# 08.net
KiCad netlist of a schematic drawn in Altium Designer
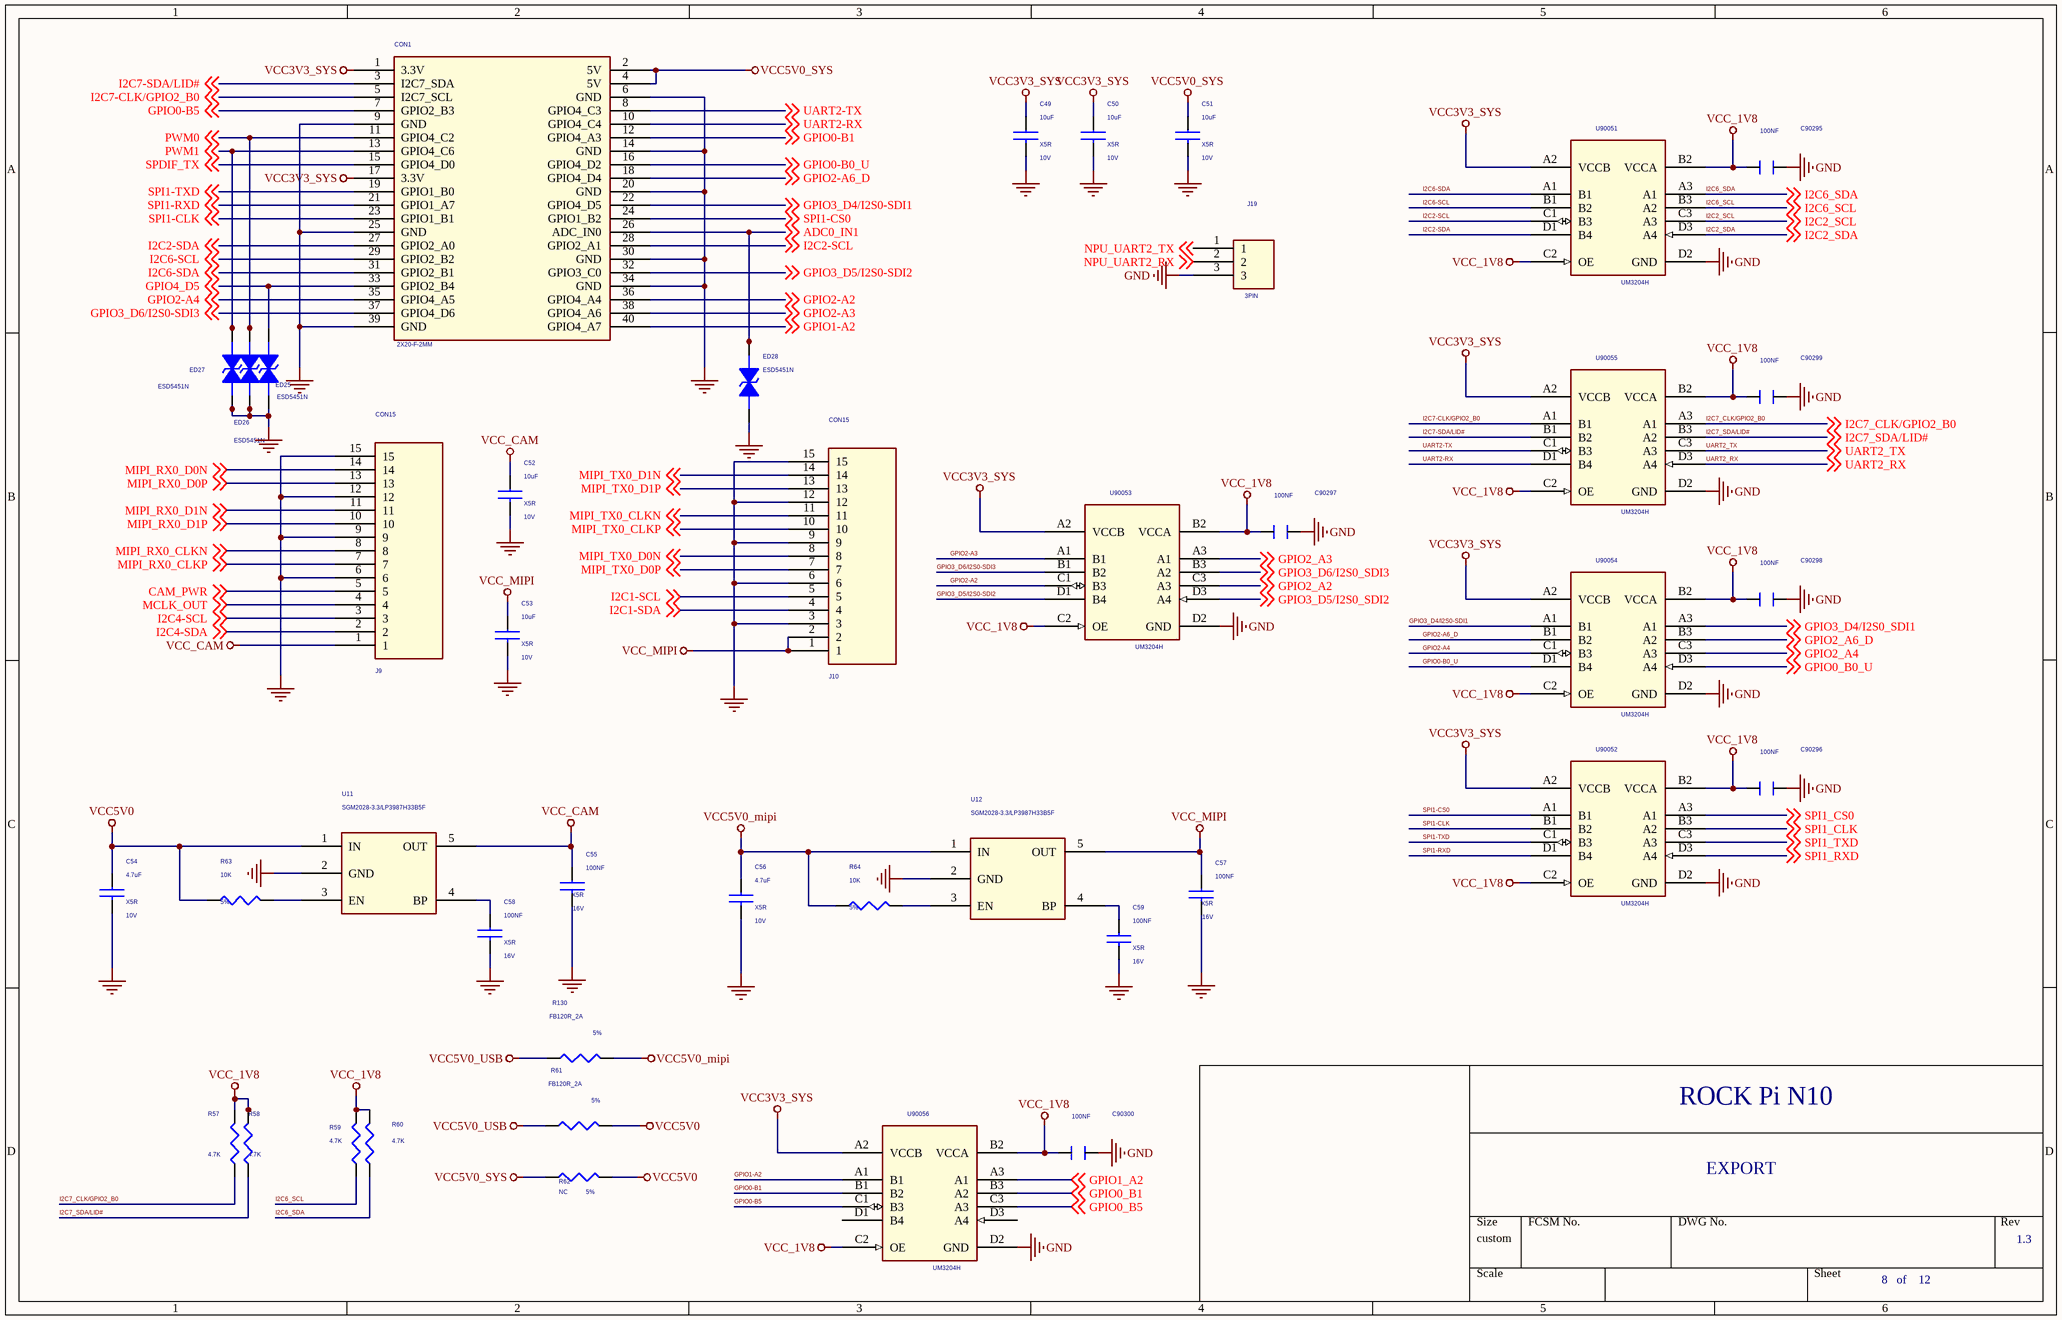
[diagram p0: 08.SchDoc]

(export (version "E")
  (design (tool "Eeschema 10.0.6"))
  (components
    (comp (ref "C49")
      (value "10uF")
      (footprint "C0603")
      (description "cap,10.00uF,+/-10%,10V,X5R,C0805")
      (fields
        (field (name "DIELECTRIC") "X5R")
        (field (name "VOLTAGE") "10V")
        (field (name "MANUFACTURER") "TDK")
        (field (name "TOLERANCE") "10%")
        (field (name "CREATED BY") "JJJ")
      )
      (libsource (lib "*") (part "CAP NP_2"))
    )
    (comp (ref "C50")
      (value "10uF")
      (footprint "C0603")
      (description "cap,10.00uF,+/-10%,10V,X5R,C0805")
      (fields
        (field (name "DIELECTRIC") "X5R")
        (field (name "VOLTAGE") "10V")
        (field (name "TOLERANCE") "10%")
        (field (name "MANUFACTURER") "TDK")
        (field (name "CREATED BY") "JJJ")
      )
      (libsource (lib "*") (part "CAP NP_2"))
    )
    (comp (ref "C51")
      (value "10uF")
      (footprint "C0603")
      (description "cap,10.00uF,+/-10%,10V,X5R,C0805")
      (fields
        (field (name "DIELECTRIC") "X5R")
        (field (name "VOLTAGE") "10V")
        (field (name "TOLERANCE") "10%")
        (field (name "MANUFACTURER") "TDK")
        (field (name "CREATED BY") "JJJ")
      )
      (libsource (lib "*") (part "CAP NP_2"))
    )
    (comp (ref "C52")
      (value "10uF")
      (footprint "C0603")
      (description "cap,10.00uF,+/-10%,10V,X5R,C0805")
      (fields
        (field (name "DIELECTRIC") "X5R")
        (field (name "VOLTAGE") "10V")
        (field (name "MANUFACTURER") "TDK")
        (field (name "TOLERANCE") "10%")
        (field (name "CREATED BY") "JJJ")
      )
      (libsource (lib "*") (part "CAP NP_2"))
    )
    (comp (ref "C53")
      (value "10uF")
      (footprint "C0603")
      (description "cap,10.00uF,+/-10%,10V,X5R,C0805")
      (fields
        (field (name "DIELECTRIC") "X5R")
        (field (name "VOLTAGE") "10V")
        (field (name "TOLERANCE") "10%")
        (field (name "MANUFACTURER") "TDK")
        (field (name "CREATED BY") "JJJ")
      )
      (libsource (lib "*") (part "CAP NP_2"))
    )
    (comp (ref "C54")
      (value "4.7uF")
      (footprint "C0603")
      (description "cap,4.70uF,+/-10%,10V,X5R,C0603")
      (fields
        (field (name "DIELECTRIC") "X5R")
        (field (name "VOLTAGE") "10V")
        (field (name "TOLERANCE") "10%")
        (field (name "MANUFACTURER") "TDK")
        (field (name "CREATED BY") "JJJ")
      )
      (libsource (lib "*") (part "CAP NP_2"))
    )
    (comp (ref "C55")
      (value "100NF")
      (footprint "C0402")
      (description "cap,100.00nF,+/-10%,16V,X5R,C0402")
      (fields
        (field (name "DIELECTRIC") "X5R")
        (field (name "VOLTAGE") "16V")
        (field (name "TOLERANCE") "10%")
        (field (name "MANUFACTURER") "TDK")
        (field (name "CREATED BY") "JJJ")
      )
      (libsource (lib "*") (part "CAP NP_2"))
    )
    (comp (ref "C56")
      (value "4.7uF")
      (footprint "C0603")
      (description "cap,4.70uF,+/-10%,10V,X5R,C0603")
      (fields
        (field (name "DIELECTRIC") "X5R")
        (field (name "VOLTAGE") "10V")
        (field (name "TOLERANCE") "10%")
        (field (name "MANUFACTURER") "TDK")
        (field (name "CREATED BY") "JJJ")
      )
      (libsource (lib "*") (part "CAP NP_2"))
    )
    (comp (ref "C57")
      (value "100NF")
      (footprint "C0402")
      (description "cap,100.00nF,+/-10%,16V,X5R,C0402")
      (fields
        (field (name "DIELECTRIC") "X5R")
        (field (name "VOLTAGE") "16V")
        (field (name "MANUFACTURER") "TDK")
        (field (name "TOLERANCE") "10%")
        (field (name "CREATED BY") "JJJ")
      )
      (libsource (lib "*") (part "CAP NP_2"))
    )
    (comp (ref "C58")
      (value "100NF")
      (footprint "C0402")
      (description "cap,100.00nF,+/-10%,16V,X5R,C0402")
      (fields
        (field (name "DIELECTRIC") "X5R")
        (field (name "VOLTAGE") "16V")
        (field (name "TOLERANCE") "10%")
        (field (name "MANUFACTURER") "TDK")
        (field (name "CREATED BY") "JJJ")
      )
      (libsource (lib "*") (part "CAP NP_2"))
    )
    (comp (ref "C59")
      (value "100NF")
      (footprint "C0402")
      (description "cap,100.00nF,+/-10%,16V,X5R,C0402")
      (fields
        (field (name "DIELECTRIC") "X5R")
        (field (name "VOLTAGE") "16V")
        (field (name "TOLERANCE") "10%")
        (field (name "MANUFACTURER") "TDK")
        (field (name "CREATED BY") "JJJ")
      )
      (libsource (lib "*") (part "CAP NP_2"))
    )
    (comp (ref "C90295") (value "100NF") (footprint "C0402") (libsource (lib "*") (part "CAPACITOR_0")))
    (comp (ref "C90296") (value "100NF") (footprint "C0402") (libsource (lib "*") (part "CAPACITOR_0")))
    (comp (ref "C90297") (value "100NF") (footprint "C0402") (libsource (lib "*") (part "CAPACITOR_0")))
    (comp (ref "C90298") (value "100NF") (footprint "C0402") (libsource (lib "*") (part "CAPACITOR_0")))
    (comp (ref "C90299") (value "100NF") (footprint "C0402") (libsource (lib "*") (part "CAPACITOR_0")))
    (comp (ref "C90300") (value "100NF") (footprint "C0402") (libsource (lib "*") (part "CAPACITOR_0")))
    (comp (ref "CON1")
      (value "2X20-F-2MM")
      (footprint "DIP40PIN-2.54MM_FX")
      (libsource (lib "*") (part "CN_4"))
    )
    (comp (ref "ED25")
      (value "ESD5451N")
      (footprint "ESD0402")
      (description "1-Line, Bi-directional, Transient Voltage Suppressors.17.5pF.")
      (fields (field (name "MANUFACTURER") "WillSemi(韦尔半导体)") (field (name "CREATED BY") "JJJ"))
      (libsource (lib "*") (part "DIODE BI_DIR TRIG_0"))
    )
    (comp (ref "ED26")
      (value "ESD5451N")
      (footprint "ESD0402")
      (description "1-Line, Bi-directional, Transient Voltage Suppressors.17.5pF.")
      (fields (field (name "MANUFACTURER") "WillSemi(韦尔半导体)") (field (name "CREATED BY") "JJJ"))
      (libsource (lib "*") (part "DIODE BI_DIR TRIG_0"))
    )
    (comp (ref "ED27")
      (value "ESD5451N")
      (footprint "ESD0402")
      (description "1-Line, Bi-directional, Transient Voltage Suppressors.17.5pF.")
      (fields (field (name "MANUFACTURER") "WillSemi(韦尔半导体)") (field (name "CREATED BY") "JJJ"))
      (libsource (lib "*") (part "DIODE BI_DIR TRIG_0"))
    )
    (comp (ref "ED28")
      (value "ESD5451N")
      (footprint "ESD0402")
      (description "1-Line, Bi-directional, Transient Voltage Suppressors.17.5pF.")
      (fields (field (name "MANUFACTURER") "WillSemi(韦尔半导体)") (field (name "CREATED BY") "JJJ"))
      (libsource (lib "*") (part "DIODE BI_DIR TRIG_0"))
    )
    (comp (ref "J9") (value "CON15") (footprint "FPC15PIN-1.0MM-LS") (libsource (lib "*") (part "CON15_0")))
    (comp (ref "J10") (value "CON15") (footprint "FPC15PIN-1.0MM-LS") (libsource (lib "*") (part "CON15_0")))
    (comp (ref "J19") (value "3PIN") (footprint "3PIN") (libsource (lib "*") (part "3PIN")))
    (comp (ref "R57") (value "4.7K") (footprint "R0402") (libsource (lib "*") (part "R_2")))
    (comp (ref "R58") (value "4.7K") (footprint "R0402") (libsource (lib "*") (part "R_2")))
    (comp (ref "R59") (value "4.7K") (footprint "R0402") (libsource (lib "*") (part "R_2")))
    (comp (ref "R60") (value "4.7K") (footprint "R0402") (libsource (lib "*") (part "R_2")))
    (comp (ref "R61")
      (value "FB120R_2A")
      (footprint "R0402")
      (description "通用厚膜电阻,10K,+/-5%,R0402,1/16W.")
      (fields
        (field (name "TOLERANCE") "5%")
        (field (name "MANUFACTURER") "YAGEO")
        (field (name "CREATED BY") "YTL")
      )
      (libsource (lib "*") (part "RESISTOR_3"))
    )
    (comp (ref "R62")
      (value "NC")
      (footprint "R0402")
      (description "通用厚膜电阻,10K,+/-5%,R0402,1/16W.")
      (fields
        (field (name "TOLERANCE") "5%")
        (field (name "MANUFACTURER") "YAGEO")
        (field (name "CREATED BY") "YTL")
      )
      (libsource (lib "*") (part "RESISTOR_3"))
    )
    (comp (ref "R63")
      (value "10K")
      (footprint "R0402")
      (description "通用厚膜电阻,10K,+/-5%,R0402,1/16W.")
      (fields
        (field (name "TOLERANCE") "5%")
        (field (name "MANUFACTURER") "YAGEO")
        (field (name "CREATED BY") "YTL")
      )
      (libsource (lib "*") (part "RESISTOR_3"))
    )
    (comp (ref "R64")
      (value "10K")
      (footprint "R0402")
      (description "通用厚膜电阻,10K,+/-5%,R0402,1/16W.")
      (fields
        (field (name "TOLERANCE") "5%")
        (field (name "MANUFACTURER") "YAGEO")
        (field (name "CREATED BY") "YTL")
      )
      (libsource (lib "*") (part "RESISTOR_3"))
    )
    (comp (ref "R130")
      (value "FB120R_2A")
      (footprint "R0402")
      (description "通用厚膜电阻,10K,+/-5%,R0402,1/16W.")
      (fields
        (field (name "TOLERANCE") "5%")
        (field (name "MANUFACTURER") "YAGEO")
        (field (name "CREATED BY") "YTL")
      )
      (libsource (lib "*") (part "RESISTOR_3"))
    )
    (comp (ref "U11")
      (value "SGM2028-3.3/LP3987H33B5F")
      (footprint "SOT_23_5")
      (description "500mA, Low Dropout, Low Noise Ultra-Fast Without Bypass Capacitor CMOS LDO Regulator")
      (fields (field (name "MANUFACTURER") "Richtek（立錡）") (field (name "CREATED BY") "JJJ"))
      (libsource (lib "*") (part "LDO_PT5108"))
    )
    (comp (ref "U12")
      (value "SGM2028-3.3/LP3987H33B5F")
      (footprint "SOT_23_5")
      (description "500mA, Low Dropout, Low Noise Ultra-Fast Without Bypass Capacitor CMOS LDO Regulator")
      (fields (field (name "MANUFACTURER") "Richtek（立錡）") (field (name "CREATED BY") "JJJ"))
      (libsource (lib "*") (part "LDO_PT5108"))
    )
    (comp (ref "U90051")
      (value "UM3204H")
      (footprint "CSP-12")
      (description "4-bit Bi-directional Level Shifter UM3204H")
      (fields (field (name "PART NUMBER") "PI4ULS5V104GAEX"))
      (libsource (lib "*") (part "MP2610_0"))
    )
    (comp (ref "U90052")
      (value "UM3204H")
      (footprint "CSP-12")
      (description "4-bit Bi-directional Level Shifter  UM3204H")
      (fields (field (name "PART NUMBER") "PI4ULS5V104GAEX"))
      (libsource (lib "*") (part "MP2610_0"))
    )
    (comp (ref "U90053")
      (value "UM3204H")
      (footprint "CSP-12")
      (description "4-bit Bi-directional Level Shifter  UM3204H")
      (fields (field (name "PART NUMBER") "PI4ULS5V104GAEX"))
      (libsource (lib "*") (part "MP2610_0"))
    )
    (comp (ref "U90054")
      (value "UM3204H")
      (footprint "CSP-12")
      (description "4-bit Bi-directional Level Shifter   UM3204H")
      (fields (field (name "PART NUMBER") "PI4ULS5V104GAEX"))
      (libsource (lib "*") (part "MP2610_0"))
    )
    (comp (ref "U90055")
      (value "UM3204H")
      (footprint "CSP-12")
      (description "4-bit Bi-directional Level Shifter UM3204H")
      (fields (field (name "PART NUMBER") "PI4ULS5V104GAEX"))
      (libsource (lib "*") (part "MP2610_0"))
    )
    (comp (ref "U90056")
      (value "UM3204H")
      (footprint "CSP-12")
      (description "4-bit Bi-directional Level Shifter  UM3204H")
      (fields (field (name "PART NUMBER") "PI4ULS5V104GAEX"))
      (libsource (lib "*") (part "MP2610_0"))
    )
  )
  (nets
    (net (code "1") (name "ADC0_IN1") (class "Default")
      (node (ref "CON1") (pin "26") (pinfunction "ADC_IN0_26") (pintype "passive"))
      (node (ref "ED28") (pin "1") (pinfunction "1_1") (pintype "passive"))
    )
    (net (code "2") (name "CAM_PWR") (class "Default")
      (node (ref "J9") (pin "5") (pinfunction "5_5") (pintype "passive"))
    )
    (net (code "3") (name "GND") (class "Default")
      (node (ref "C49") (pin "2") (pinfunction "2_2") (pintype "passive"))
      (node (ref "C50") (pin "2") (pinfunction "2_2") (pintype "passive"))
      (node (ref "C51") (pin "2") (pinfunction "2_2") (pintype "passive"))
      (node (ref "C52") (pin "2") (pinfunction "2_2") (pintype "passive"))
      (node (ref "C53") (pin "2") (pinfunction "2_2") (pintype "passive"))
      (node (ref "C54") (pin "2") (pinfunction "2_2") (pintype "passive"))
      (node (ref "C55") (pin "2") (pinfunction "2_2") (pintype "passive"))
      (node (ref "C56") (pin "2") (pinfunction "2_2") (pintype "passive"))
      (node (ref "C57") (pin "2") (pinfunction "2_2") (pintype "passive"))
      (node (ref "C58") (pin "2") (pinfunction "2_2") (pintype "passive"))
      (node (ref "C59") (pin "2") (pinfunction "2_2") (pintype "passive"))
      (node (ref "C90295") (pin "1") (pinfunction "1_1") (pintype "passive"))
      (node (ref "C90296") (pin "1") (pinfunction "1_1") (pintype "passive"))
      (node (ref "C90297") (pin "1") (pinfunction "1_1") (pintype "passive"))
      (node (ref "C90298") (pin "1") (pinfunction "1_1") (pintype "passive"))
      (node (ref "C90299") (pin "1") (pinfunction "1_1") (pintype "passive"))
      (node (ref "C90300") (pin "1") (pinfunction "1_1") (pintype "passive"))
      (node (ref "CON1") (pin "14") (pinfunction "GND_14") (pintype "passive"))
      (node (ref "CON1") (pin "20") (pinfunction "GND_20") (pintype "passive"))
      (node (ref "CON1") (pin "25") (pinfunction "GND_25") (pintype "passive"))
      (node (ref "CON1") (pin "30") (pinfunction "GND_30") (pintype "passive"))
      (node (ref "CON1") (pin "34") (pinfunction "GND_34") (pintype "passive"))
      (node (ref "CON1") (pin "39") (pinfunction "GND_39") (pintype "passive"))
      (node (ref "CON1") (pin "6") (pinfunction "GND_6") (pintype "passive"))
      (node (ref "CON1") (pin "9") (pinfunction "GND_9") (pintype "passive"))
      (node (ref "ED25") (pin "2") (pinfunction "2_2") (pintype "passive"))
      (node (ref "ED26") (pin "2") (pinfunction "2_2") (pintype "passive"))
      (node (ref "ED27") (pin "2") (pinfunction "2_2") (pintype "passive"))
      (node (ref "ED28") (pin "2") (pinfunction "2_2") (pintype "passive"))
      (node (ref "J10") (pin "12") (pinfunction "12_12") (pintype "passive"))
      (node (ref "J10") (pin "15") (pinfunction "15_15") (pintype "passive"))
      (node (ref "J10") (pin "3") (pinfunction "3_3") (pintype "passive"))
      (node (ref "J10") (pin "6") (pinfunction "6_6") (pintype "passive"))
      (node (ref "J10") (pin "9") (pinfunction "9_9") (pintype "passive"))
      (node (ref "J19") (pin "3") (pinfunction "3_3") (pintype "passive"))
      (node (ref "J9") (pin "12") (pinfunction "12_12") (pintype "passive"))
      (node (ref "J9") (pin "15") (pinfunction "15_15") (pintype "passive"))
      (node (ref "J9") (pin "6") (pinfunction "6_6") (pintype "passive"))
      (node (ref "J9") (pin "9") (pinfunction "9_9") (pintype "passive"))
      (node (ref "U11") (pin "2") (pinfunction "GND_2") (pintype "passive"))
      (node (ref "U12") (pin "2") (pinfunction "GND_2") (pintype "passive"))
      (node (ref "U90051") (pin "D2") (pinfunction "GND_D2") (pintype "power_in"))
      (node (ref "U90052") (pin "D2") (pinfunction "GND_D2") (pintype "power_in"))
      (node (ref "U90053") (pin "D2") (pinfunction "GND_D2") (pintype "power_in"))
      (node (ref "U90054") (pin "D2") (pinfunction "GND_D2") (pintype "power_in"))
      (node (ref "U90055") (pin "D2") (pinfunction "GND_D2") (pintype "power_in"))
      (node (ref "U90056") (pin "D2") (pinfunction "GND_D2") (pintype "power_in"))
    )
    (net (code "4") (name "GPIO0-B0_U") (class "Default")
      (node (ref "CON1") (pin "16") (pinfunction "GPIO4_D2_16") (pintype "passive"))
      (node (ref "U90054") (pin "D1") (pinfunction "B4_D1") (pintype "tri_state"))
    )
    (net (code "5") (name "GPIO0-B1") (class "Default")
      (node (ref "CON1") (pin "12") (pinfunction "GPIO4_A3_12") (pintype "passive"))
      (node (ref "U90056") (pin "B1") (pinfunction "B2_B1") (pintype "tri_state"))
    )
    (net (code "6") (name "GPIO0-B5") (class "Default")
      (node (ref "CON1") (pin "7") (pinfunction "GPIO2_B3_7") (pintype "passive"))
      (node (ref "U90056") (pin "C1") (pinfunction "B3_C1") (pintype "bidirectional"))
    )
    (net (code "7") (name "GPIO0_B0_U") (class "Default")
      (node (ref "U90054") (pin "D3") (pinfunction "A4_D3") (pintype "input"))
    )
    (net (code "8") (name "GPIO0_B1") (class "Default")
      (node (ref "U90056") (pin "B3") (pinfunction "A2_B3") (pintype "tri_state"))
    )
    (net (code "9") (name "GPIO0_B5") (class "Default")
      (node (ref "U90056") (pin "C3") (pinfunction "A3_C3") (pintype "tri_state"))
    )
    (net (code "10") (name "GPIO1-A2") (class "Default")
      (node (ref "CON1") (pin "40") (pinfunction "GPIO4_A7_40") (pintype "passive"))
      (node (ref "U90056") (pin "A1") (pinfunction "B1_A1") (pintype "tri_state"))
    )
    (net (code "11") (name "GPIO1_A2") (class "Default")
      (node (ref "U90056") (pin "A3") (pinfunction "A1_A3") (pintype "tri_state"))
    )
    (net (code "12") (name "GPIO2-A2") (class "Default")
      (node (ref "CON1") (pin "36") (pinfunction "GPIO4_A4_36") (pintype "passive"))
      (node (ref "U90053") (pin "C1") (pinfunction "B3_C1") (pintype "bidirectional"))
    )
    (net (code "13") (name "GPIO2-A3") (class "Default")
      (node (ref "CON1") (pin "38") (pinfunction "GPIO4_A6_38") (pintype "passive"))
      (node (ref "U90053") (pin "A1") (pinfunction "B1_A1") (pintype "tri_state"))
    )
    (net (code "14") (name "GPIO2-A4") (class "Default")
      (node (ref "CON1") (pin "35") (pinfunction "GPIO4_A5_35") (pintype "passive"))
      (node (ref "U90054") (pin "C1") (pinfunction "B3_C1") (pintype "bidirectional"))
    )
    (net (code "15") (name "GPIO2-A6_D") (class "Default")
      (node (ref "CON1") (pin "18") (pinfunction "GPIO4_D4_18") (pintype "passive"))
      (node (ref "U90054") (pin "B1") (pinfunction "B2_B1") (pintype "tri_state"))
    )
    (net (code "16") (name "GPIO2_A2") (class "Default")
      (node (ref "U90053") (pin "C3") (pinfunction "A3_C3") (pintype "tri_state"))
    )
    (net (code "17") (name "GPIO2_A3") (class "Default")
      (node (ref "U90053") (pin "A3") (pinfunction "A1_A3") (pintype "tri_state"))
    )
    (net (code "18") (name "GPIO2_A4") (class "Default")
      (node (ref "U90054") (pin "C3") (pinfunction "A3_C3") (pintype "tri_state"))
    )
    (net (code "19") (name "GPIO2_A6_D") (class "Default")
      (node (ref "U90054") (pin "B3") (pinfunction "A2_B3") (pintype "tri_state"))
    )
    (net (code "20") (name "GPIO3_D4{slash}I2S0-SDI1") (class "Default")
      (node (ref "CON1") (pin "22") (pinfunction "GPIO4_D5_22") (pintype "passive"))
      (node (ref "U90054") (pin "A1") (pinfunction "B1_A1") (pintype "tri_state"))
    )
    (net (code "21") (name "GPIO3_D4{slash}I2S0_SDI1") (class "Default")
      (node (ref "U90054") (pin "A3") (pinfunction "A1_A3") (pintype "tri_state"))
    )
    (net (code "22") (name "GPIO3_D5{slash}I2S0-SDI2") (class "Default")
      (node (ref "CON1") (pin "32") (pinfunction "GPIO3_C0_32") (pintype "passive"))
      (node (ref "U90053") (pin "D1") (pinfunction "B4_D1") (pintype "tri_state"))
    )
    (net (code "23") (name "GPIO3_D5{slash}I2S0_SDI2") (class "Default")
      (node (ref "U90053") (pin "D3") (pinfunction "A4_D3") (pintype "input"))
    )
    (net (code "24") (name "GPIO3_D6{slash}I2S0-SDI3") (class "Default")
      (node (ref "CON1") (pin "37") (pinfunction "GPIO4_D6_37") (pintype "passive"))
      (node (ref "U90053") (pin "B1") (pinfunction "B2_B1") (pintype "tri_state"))
    )
    (net (code "25") (name "GPIO3_D6{slash}I2S0_SDI3") (class "Default")
      (node (ref "U90053") (pin "B3") (pinfunction "A2_B3") (pintype "tri_state"))
    )
    (net (code "26") (name "GPIO4_D5") (class "Default")
      (node (ref "CON1") (pin "33") (pinfunction "GPIO2_B4_33") (pintype "passive"))
      (node (ref "ED25") (pin "1") (pinfunction "1_1") (pintype "passive"))
    )
    (net (code "27") (name "I2C1-SCL") (class "Default")
      (node (ref "J10") (pin "5") (pinfunction "5_5") (pintype "passive"))
    )
    (net (code "28") (name "I2C1-SDA") (class "Default")
      (node (ref "J10") (pin "4") (pinfunction "4_4") (pintype "passive"))
    )
    (net (code "29") (name "I2C2-SCL") (class "Default")
      (node (ref "CON1") (pin "28") (pinfunction "GPIO2_A1_28") (pintype "passive"))
      (node (ref "U90051") (pin "C1") (pinfunction "B3_C1") (pintype "bidirectional"))
    )
    (net (code "30") (name "I2C2-SDA") (class "Default")
      (node (ref "CON1") (pin "27") (pinfunction "GPIO2_A0_27") (pintype "passive"))
      (node (ref "U90051") (pin "D1") (pinfunction "B4_D1") (pintype "tri_state"))
    )
    (net (code "31") (name "I2C2_SCL") (class "Default")
      (node (ref "U90051") (pin "C3") (pinfunction "A3_C3") (pintype "tri_state"))
    )
    (net (code "32") (name "I2C2_SDA") (class "Default")
      (node (ref "U90051") (pin "D3") (pinfunction "A4_D3") (pintype "input"))
    )
    (net (code "33") (name "I2C4-SCL") (class "Default")
      (node (ref "J9") (pin "3") (pinfunction "3_3") (pintype "passive"))
    )
    (net (code "34") (name "I2C4-SDA") (class "Default")
      (node (ref "J9") (pin "2") (pinfunction "2_2") (pintype "passive"))
    )
    (net (code "35") (name "I2C6-SCL") (class "Default")
      (node (ref "CON1") (pin "29") (pinfunction "GPIO2_B2_29") (pintype "passive"))
      (node (ref "U90051") (pin "B1") (pinfunction "B2_B1") (pintype "tri_state"))
    )
    (net (code "36") (name "I2C6-SDA") (class "Default")
      (node (ref "CON1") (pin "31") (pinfunction "GPIO2_B1_31") (pintype "passive"))
      (node (ref "U90051") (pin "A1") (pinfunction "B1_A1") (pintype "tri_state"))
    )
    (net (code "37") (name "I2C6_SCL") (class "Default")
      (node (ref "R59") (pin "1") (pinfunction "1_1") (pintype "passive"))
      (node (ref "U90051") (pin "B3") (pinfunction "A2_B3") (pintype "tri_state"))
    )
    (net (code "38") (name "I2C6_SDA") (class "Default")
      (node (ref "R60") (pin "1") (pinfunction "1_1") (pintype "passive"))
      (node (ref "U90051") (pin "A3") (pinfunction "A1_A3") (pintype "tri_state"))
    )
    (net (code "39") (name "I2C7-CLK{slash}GPIO2_B0") (class "Default")
      (node (ref "CON1") (pin "5") (pinfunction "I2C7_SCL_5") (pintype "passive"))
      (node (ref "U90055") (pin "A1") (pinfunction "B1_A1") (pintype "tri_state"))
    )
    (net (code "40") (name "I2C7-SDA{slash}LID#") (class "Default")
      (node (ref "CON1") (pin "3") (pinfunction "I2C7_SDA_3") (pintype "passive"))
      (node (ref "U90055") (pin "B1") (pinfunction "B2_B1") (pintype "tri_state"))
    )
    (net (code "41") (name "I2C7_CLK{slash}GPIO2_B0") (class "Default")
      (node (ref "R57") (pin "1") (pinfunction "1_1") (pintype "passive"))
      (node (ref "U90055") (pin "A3") (pinfunction "A1_A3") (pintype "tri_state"))
    )
    (net (code "42") (name "I2C7_SDA{slash}LID#") (class "Default")
      (node (ref "R58") (pin "1") (pinfunction "1_1") (pintype "passive"))
      (node (ref "U90055") (pin "B3") (pinfunction "A2_B3") (pintype "tri_state"))
    )
    (net (code "43") (name "MCLK_OUT") (class "Default")
      (node (ref "J9") (pin "4") (pinfunction "4_4") (pintype "passive"))
    )
    (net (code "44") (name "MIPI_RX0_CLKN") (class "Default")
      (node (ref "J9") (pin "8") (pinfunction "8_8") (pintype "passive"))
    )
    (net (code "45") (name "MIPI_RX0_CLKP") (class "Default")
      (node (ref "J9") (pin "7") (pinfunction "7_7") (pintype "passive"))
    )
    (net (code "46") (name "MIPI_RX0_D0N") (class "Default")
      (node (ref "J9") (pin "14") (pinfunction "14_14") (pintype "passive"))
    )
    (net (code "47") (name "MIPI_RX0_D0P") (class "Default")
      (node (ref "J9") (pin "13") (pinfunction "13_13") (pintype "passive"))
    )
    (net (code "48") (name "MIPI_RX0_D1N") (class "Default")
      (node (ref "J9") (pin "11") (pinfunction "11_11") (pintype "passive"))
    )
    (net (code "49") (name "MIPI_RX0_D1P") (class "Default")
      (node (ref "J9") (pin "10") (pinfunction "10_10") (pintype "passive"))
    )
    (net (code "50") (name "MIPI_TX0_CLKN") (class "Default")
      (node (ref "J10") (pin "11") (pinfunction "11_11") (pintype "passive"))
    )
    (net (code "51") (name "MIPI_TX0_CLKP") (class "Default")
      (node (ref "J10") (pin "10") (pinfunction "10_10") (pintype "passive"))
    )
    (net (code "52") (name "MIPI_TX0_D0N") (class "Default")
      (node (ref "J10") (pin "8") (pinfunction "8_8") (pintype "passive"))
    )
    (net (code "53") (name "MIPI_TX0_D0P") (class "Default")
      (node (ref "J10") (pin "7") (pinfunction "7_7") (pintype "passive"))
    )
    (net (code "54") (name "MIPI_TX0_D1N") (class "Default")
      (node (ref "J10") (pin "14") (pinfunction "14_14") (pintype "passive"))
    )
    (net (code "55") (name "MIPI_TX0_D1P") (class "Default")
      (node (ref "J10") (pin "13") (pinfunction "13_13") (pintype "passive"))
    )
    (net (code "56") (name "NPU_UART2_RX") (class "Default")
      (node (ref "J19") (pin "2") (pinfunction "2_2") (pintype "passive"))
    )
    (net (code "57") (name "NPU_UART2_TX") (class "Default")
      (node (ref "J19") (pin "1") (pinfunction "1_1") (pintype "passive"))
    )
    (net (code "58") (name "Net-(U11-BP)") (class "Default")
      (node (ref "C58") (pin "1") (pinfunction "1_1") (pintype "passive"))
      (node (ref "U11") (pin "4") (pinfunction "BP_4") (pintype "passive"))
    )
    (net (code "59") (name "Net-(U11-EN)") (class "Default")
      (node (ref "R63") (pin "2") (pinfunction "2_2") (pintype "passive"))
      (node (ref "U11") (pin "3") (pinfunction "EN_3") (pintype "passive"))
    )
    (net (code "60") (name "Net-(U12-BP)") (class "Default")
      (node (ref "C59") (pin "1") (pinfunction "1_1") (pintype "passive"))
      (node (ref "U12") (pin "4") (pinfunction "BP_4") (pintype "passive"))
    )
    (net (code "61") (name "Net-(U12-EN)") (class "Default")
      (node (ref "R64") (pin "2") (pinfunction "2_2") (pintype "passive"))
      (node (ref "U12") (pin "3") (pinfunction "EN_3") (pintype "passive"))
    )
    (net (code "62") (name "PWM0") (class "Default")
      (node (ref "CON1") (pin "11") (pinfunction "GPIO4_C2_11") (pintype "passive"))
      (node (ref "ED26") (pin "1") (pinfunction "1_1") (pintype "passive"))
    )
    (net (code "63") (name "PWM1") (class "Default")
      (node (ref "CON1") (pin "13") (pinfunction "GPIO4_C6_13") (pintype "passive"))
      (node (ref "ED27") (pin "1") (pinfunction "1_1") (pintype "passive"))
    )
    (net (code "64") (name "SPDIF_TX") (class "Default")
      (node (ref "CON1") (pin "15") (pinfunction "GPIO4_D0_15") (pintype "passive"))
    )
    (net (code "65") (name "SPI1-CLK") (class "Default")
      (node (ref "CON1") (pin "23") (pinfunction "GPIO1_B1_23") (pintype "passive"))
      (node (ref "U90052") (pin "B1") (pinfunction "B2_B1") (pintype "tri_state"))
    )
    (net (code "66") (name "SPI1-CS0") (class "Default")
      (node (ref "CON1") (pin "24") (pinfunction "GPIO1_B2_24") (pintype "passive"))
      (node (ref "U90052") (pin "A1") (pinfunction "B1_A1") (pintype "tri_state"))
    )
    (net (code "67") (name "SPI1-RXD") (class "Default")
      (node (ref "CON1") (pin "21") (pinfunction "GPIO1_A7_21") (pintype "passive"))
      (node (ref "U90052") (pin "D1") (pinfunction "B4_D1") (pintype "tri_state"))
    )
    (net (code "68") (name "SPI1-TXD") (class "Default")
      (node (ref "CON1") (pin "19") (pinfunction "GPIO1_B0_19") (pintype "passive"))
      (node (ref "U90052") (pin "C1") (pinfunction "B3_C1") (pintype "bidirectional"))
    )
    (net (code "69") (name "SPI1_CLK") (class "Default")
      (node (ref "U90052") (pin "B3") (pinfunction "A2_B3") (pintype "tri_state"))
    )
    (net (code "70") (name "SPI1_CS0") (class "Default")
      (node (ref "U90052") (pin "A3") (pinfunction "A1_A3") (pintype "tri_state"))
    )
    (net (code "71") (name "SPI1_RXD") (class "Default")
      (node (ref "U90052") (pin "D3") (pinfunction "A4_D3") (pintype "input"))
    )
    (net (code "72") (name "SPI1_TXD") (class "Default")
      (node (ref "U90052") (pin "C3") (pinfunction "A3_C3") (pintype "tri_state"))
    )
    (net (code "73") (name "UART2-RX") (class "Default")
      (node (ref "CON1") (pin "10") (pinfunction "GPIO4_C4_10") (pintype "passive"))
      (node (ref "U90055") (pin "D1") (pinfunction "B4_D1") (pintype "tri_state"))
    )
    (net (code "74") (name "UART2-TX") (class "Default")
      (node (ref "CON1") (pin "8") (pinfunction "GPIO4_C3_8") (pintype "passive"))
      (node (ref "U90055") (pin "C1") (pinfunction "B3_C1") (pintype "bidirectional"))
    )
    (net (code "75") (name "UART2_RX") (class "Default")
      (node (ref "U90055") (pin "D3") (pinfunction "A4_D3") (pintype "input"))
    )
    (net (code "76") (name "UART2_TX") (class "Default")
      (node (ref "U90055") (pin "C3") (pinfunction "A3_C3") (pintype "tri_state"))
    )
    (net (code "77") (name "VCC3V3_SYS") (class "Default")
      (node (ref "C49") (pin "1") (pinfunction "1_1") (pintype "passive"))
      (node (ref "C50") (pin "1") (pinfunction "1_1") (pintype "passive"))
      (node (ref "CON1") (pin "1") (pinfunction "3.3V_1") (pintype "passive"))
      (node (ref "CON1") (pin "17") (pinfunction "3.3V_17") (pintype "passive"))
      (node (ref "U90051") (pin "A2") (pinfunction "VCCB_A2") (pintype "power_in"))
      (node (ref "U90052") (pin "A2") (pinfunction "VCCB_A2") (pintype "power_in"))
      (node (ref "U90053") (pin "A2") (pinfunction "VCCB_A2") (pintype "power_in"))
      (node (ref "U90054") (pin "A2") (pinfunction "VCCB_A2") (pintype "power_in"))
      (node (ref "U90055") (pin "A2") (pinfunction "VCCB_A2") (pintype "power_in"))
      (node (ref "U90056") (pin "A2") (pinfunction "VCCB_A2") (pintype "power_in"))
    )
    (net (code "78") (name "VCC5V0") (class "Default")
      (node (ref "C54") (pin "1") (pinfunction "1_1") (pintype "passive"))
      (node (ref "R61") (pin "2") (pinfunction "2_2") (pintype "passive"))
      (node (ref "R62") (pin "2") (pinfunction "2_2") (pintype "passive"))
      (node (ref "R63") (pin "1") (pinfunction "1_1") (pintype "passive"))
      (node (ref "U11") (pin "1") (pinfunction "IN_1") (pintype "passive"))
    )
    (net (code "79") (name "VCC5V0_SYS") (class "Default")
      (node (ref "C51") (pin "1") (pinfunction "1_1") (pintype "passive"))
      (node (ref "CON1") (pin "2") (pinfunction "5V_2") (pintype "passive"))
      (node (ref "CON1") (pin "4") (pinfunction "5V_4") (pintype "passive"))
      (node (ref "R62") (pin "1") (pinfunction "1_1") (pintype "passive"))
    )
    (net (code "80") (name "VCC5V0_USB") (class "Default")
      (node (ref "R130") (pin "1") (pinfunction "1_1") (pintype "passive"))
      (node (ref "R61") (pin "1") (pinfunction "1_1") (pintype "passive"))
    )
    (net (code "81") (name "VCC5V0_mipi") (class "Default")
      (node (ref "C56") (pin "1") (pinfunction "1_1") (pintype "passive"))
      (node (ref "R130") (pin "2") (pinfunction "2_2") (pintype "passive"))
      (node (ref "R64") (pin "1") (pinfunction "1_1") (pintype "passive"))
      (node (ref "U12") (pin "1") (pinfunction "IN_1") (pintype "passive"))
    )
    (net (code "82") (name "VCC_1V8") (class "Default")
      (node (ref "C90295") (pin "2") (pinfunction "2_2") (pintype "passive"))
      (node (ref "C90296") (pin "2") (pinfunction "2_2") (pintype "passive"))
      (node (ref "C90297") (pin "2") (pinfunction "2_2") (pintype "passive"))
      (node (ref "C90298") (pin "2") (pinfunction "2_2") (pintype "passive"))
      (node (ref "C90299") (pin "2") (pinfunction "2_2") (pintype "passive"))
      (node (ref "C90300") (pin "2") (pinfunction "2_2") (pintype "passive"))
      (node (ref "R57") (pin "2") (pinfunction "2_2") (pintype "passive"))
      (node (ref "R58") (pin "2") (pinfunction "2_2") (pintype "passive"))
      (node (ref "R59") (pin "2") (pinfunction "2_2") (pintype "passive"))
      (node (ref "R60") (pin "2") (pinfunction "2_2") (pintype "passive"))
      (node (ref "U90051") (pin "B2") (pinfunction "VCCA_B2") (pintype "power_in"))
      (node (ref "U90051") (pin "C2") (pinfunction "OE_C2") (pintype "input"))
      (node (ref "U90052") (pin "B2") (pinfunction "VCCA_B2") (pintype "power_in"))
      (node (ref "U90052") (pin "C2") (pinfunction "OE_C2") (pintype "input"))
      (node (ref "U90053") (pin "B2") (pinfunction "VCCA_B2") (pintype "power_in"))
      (node (ref "U90053") (pin "C2") (pinfunction "OE_C2") (pintype "input"))
      (node (ref "U90054") (pin "B2") (pinfunction "VCCA_B2") (pintype "power_in"))
      (node (ref "U90054") (pin "C2") (pinfunction "OE_C2") (pintype "input"))
      (node (ref "U90055") (pin "B2") (pinfunction "VCCA_B2") (pintype "power_in"))
      (node (ref "U90055") (pin "C2") (pinfunction "OE_C2") (pintype "input"))
      (node (ref "U90056") (pin "B2") (pinfunction "VCCA_B2") (pintype "power_in"))
      (node (ref "U90056") (pin "C2") (pinfunction "OE_C2") (pintype "input"))
    )
    (net (code "83") (name "VCC_CAM") (class "Default")
      (node (ref "C52") (pin "1") (pinfunction "1_1") (pintype "passive"))
      (node (ref "C55") (pin "1") (pinfunction "1_1") (pintype "passive"))
      (node (ref "J9") (pin "1") (pinfunction "1_1") (pintype "passive"))
      (node (ref "U11") (pin "5") (pinfunction "OUT_5") (pintype "passive"))
    )
    (net (code "84") (name "VCC_MIPI") (class "Default")
      (node (ref "C53") (pin "1") (pinfunction "1_1") (pintype "passive"))
      (node (ref "C57") (pin "1") (pinfunction "1_1") (pintype "passive"))
      (node (ref "J10") (pin "1") (pinfunction "1_1") (pintype "passive"))
      (node (ref "J10") (pin "2") (pinfunction "2_2") (pintype "passive"))
      (node (ref "U12") (pin "5") (pinfunction "OUT_5") (pintype "passive"))
    )
    (net (code "85") (name "unconnected-(U90056-A4-PadD3)") (class "Default")
      (node (ref "U90056") (pin "D3") (pinfunction "A4_D3") (pintype "input"))
    )
    (net (code "86") (name "unconnected-(U90056-B4-PadD1)") (class "Default")
      (node (ref "U90056") (pin "D1") (pinfunction "B4_D1") (pintype "tri_state"))
    )
  )
)
